# DMUX.net
KiCad netlist of a schematic drawn in EAGLE
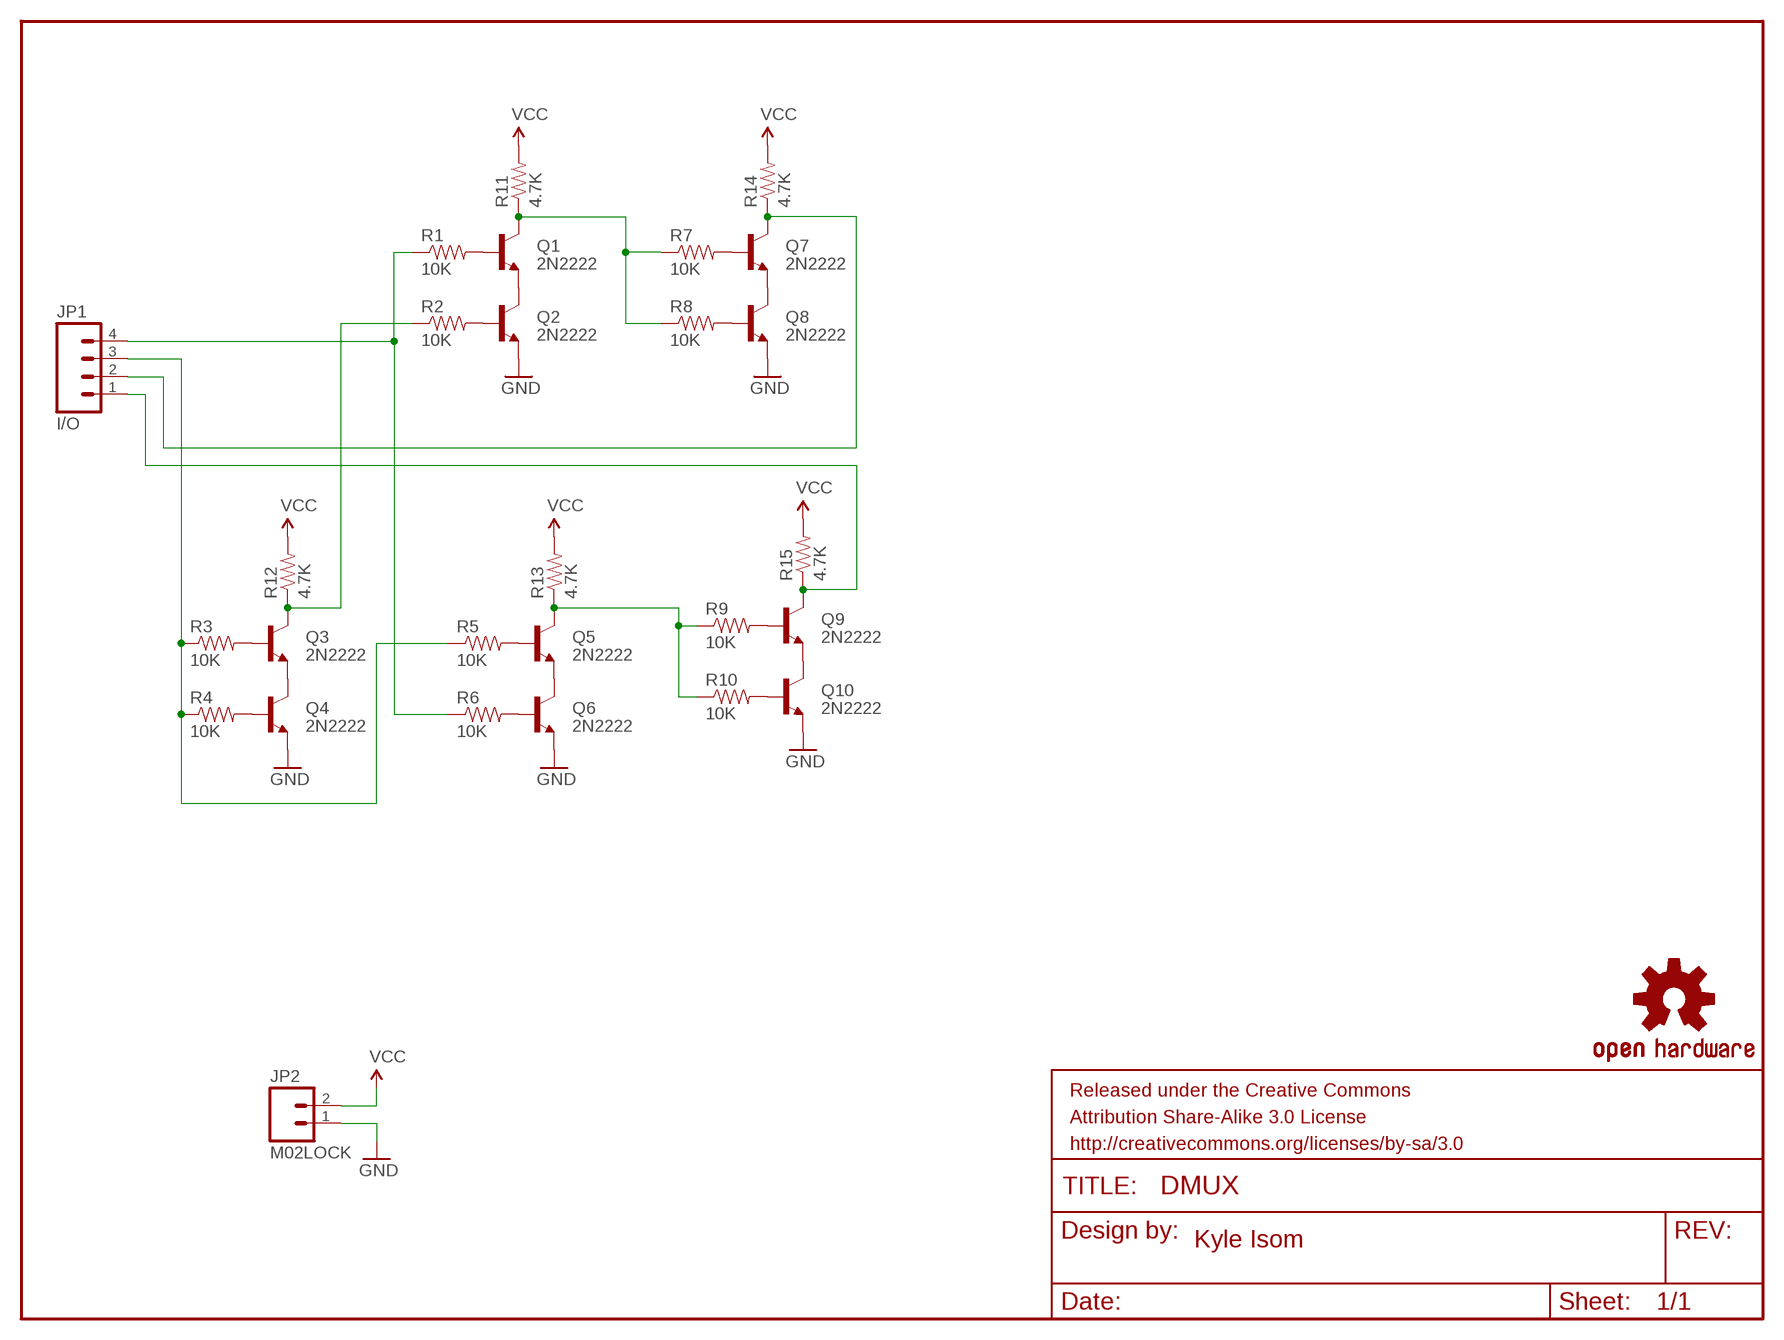
[diagram p0: schematic, sheet 1]

(export (version "E")
  (design (tool "Eeschema 10.0.6"))
  (components
    (comp (ref "FRAME1")
      (value "FRAME-LETTER")
      (footprint "eagle-import:CREATIVE_COMMONS")
      (libsource (lib "eagle-import") (part "FRAME-LETTER"))
    )
    (comp (ref "JP1")
      (value "I/O")
      (footprint "eagle-import:1X04_LOCK")
      (libsource (lib "eagle-import") (part "M04LOCK"))
    )
    (comp (ref "JP2")
      (value "M02LOCK")
      (footprint "eagle-import:1X02_LOCK")
      (libsource (lib "eagle-import") (part "M02LOCK"))
    )
    (comp (ref "LOGO1")
      (value "OSHW-LOGOS")
      (footprint "eagle-import:OSHW-LOGO-S")
      (libsource (lib "eagle-import") (part "OSHW-LOGOS"))
    )
    (comp (ref "Q1")
      (value "2N2222")
      (footprint "eagle-import:TO-92-AMMO")
      (libsource (lib "eagle-import") (part "TRANSISTOR_NPNTO-92-AMMO"))
    )
    (comp (ref "Q2")
      (value "2N2222")
      (footprint "eagle-import:TO-92-AMMO")
      (libsource (lib "eagle-import") (part "TRANSISTOR_NPNTO-92-AMMO"))
    )
    (comp (ref "Q3")
      (value "2N2222")
      (footprint "eagle-import:TO-92-AMMO")
      (libsource (lib "eagle-import") (part "TRANSISTOR_NPNTO-92-AMMO"))
    )
    (comp (ref "Q4")
      (value "2N2222")
      (footprint "eagle-import:TO-92-AMMO")
      (libsource (lib "eagle-import") (part "TRANSISTOR_NPNTO-92-AMMO"))
    )
    (comp (ref "Q5")
      (value "2N2222")
      (footprint "eagle-import:TO-92-AMMO")
      (libsource (lib "eagle-import") (part "TRANSISTOR_NPNTO-92-AMMO"))
    )
    (comp (ref "Q6")
      (value "2N2222")
      (footprint "eagle-import:TO-92-AMMO")
      (libsource (lib "eagle-import") (part "TRANSISTOR_NPNTO-92-AMMO"))
    )
    (comp (ref "Q7")
      (value "2N2222")
      (footprint "eagle-import:TO-92-AMMO")
      (libsource (lib "eagle-import") (part "TRANSISTOR_NPNTO-92-AMMO"))
    )
    (comp (ref "Q8")
      (value "2N2222")
      (footprint "eagle-import:TO-92-AMMO")
      (libsource (lib "eagle-import") (part "TRANSISTOR_NPNTO-92-AMMO"))
    )
    (comp (ref "Q9")
      (value "2N2222")
      (footprint "eagle-import:TO-92-AMMO")
      (libsource (lib "eagle-import") (part "TRANSISTOR_NPNTO-92-AMMO"))
    )
    (comp (ref "Q10")
      (value "2N2222")
      (footprint "eagle-import:TO-92-AMMO")
      (libsource (lib "eagle-import") (part "TRANSISTOR_NPNTO-92-AMMO"))
    )
    (comp (ref "R1")
      (value "10K")
      (footprint "eagle-import:AXIAL-0.4")
      (libsource (lib "eagle-import") (part "RESISTORPTH-1/4W"))
    )
    (comp (ref "R2")
      (value "10K")
      (footprint "eagle-import:AXIAL-0.4")
      (libsource (lib "eagle-import") (part "RESISTORPTH-1/4W"))
    )
    (comp (ref "R3")
      (value "10K")
      (footprint "eagle-import:AXIAL-0.4")
      (libsource (lib "eagle-import") (part "RESISTORPTH-1/4W"))
    )
    (comp (ref "R4")
      (value "10K")
      (footprint "eagle-import:AXIAL-0.4")
      (libsource (lib "eagle-import") (part "RESISTORPTH-1/4W"))
    )
    (comp (ref "R5")
      (value "10K")
      (footprint "eagle-import:AXIAL-0.4")
      (libsource (lib "eagle-import") (part "RESISTORPTH-1/4W"))
    )
    (comp (ref "R6")
      (value "10K")
      (footprint "eagle-import:AXIAL-0.4")
      (libsource (lib "eagle-import") (part "RESISTORPTH-1/4W"))
    )
    (comp (ref "R7")
      (value "10K")
      (footprint "eagle-import:AXIAL-0.4")
      (libsource (lib "eagle-import") (part "RESISTORPTH-1/4W"))
    )
    (comp (ref "R8")
      (value "10K")
      (footprint "eagle-import:AXIAL-0.4")
      (libsource (lib "eagle-import") (part "RESISTORPTH-1/4W"))
    )
    (comp (ref "R9")
      (value "10K")
      (footprint "eagle-import:AXIAL-0.4")
      (libsource (lib "eagle-import") (part "RESISTORPTH-1/4W"))
    )
    (comp (ref "R10")
      (value "10K")
      (footprint "eagle-import:AXIAL-0.4")
      (libsource (lib "eagle-import") (part "RESISTORPTH-1/4W"))
    )
    (comp (ref "R11")
      (value "4.7K")
      (footprint "eagle-import:AXIAL-0.4")
      (libsource (lib "eagle-import") (part "RESISTORPTH-1/4W"))
    )
    (comp (ref "R12")
      (value "4.7K")
      (footprint "eagle-import:AXIAL-0.4")
      (libsource (lib "eagle-import") (part "RESISTORPTH-1/4W"))
    )
    (comp (ref "R13")
      (value "4.7K")
      (footprint "eagle-import:AXIAL-0.4")
      (libsource (lib "eagle-import") (part "RESISTORPTH-1/4W"))
    )
    (comp (ref "R14")
      (value "4.7K")
      (footprint "eagle-import:AXIAL-0.4")
      (libsource (lib "eagle-import") (part "RESISTORPTH-1/4W"))
    )
    (comp (ref "R15")
      (value "4.7K")
      (footprint "eagle-import:AXIAL-0.4")
      (libsource (lib "eagle-import") (part "RESISTORPTH-1/4W"))
    )
  )
  (nets
    (net (code "1") (name "GND") (class "Default")
      (node (ref "JP2") (pin "1") (pinfunction "1_1") (pintype "passive"))
      (node (ref "Q10") (pin "1") (pinfunction "E_1") (pintype "passive"))
      (node (ref "Q2") (pin "1") (pinfunction "E_1") (pintype "passive"))
      (node (ref "Q4") (pin "1") (pinfunction "E_1") (pintype "passive"))
      (node (ref "Q6") (pin "1") (pinfunction "E_1") (pintype "passive"))
      (node (ref "Q8") (pin "1") (pinfunction "E_1") (pintype "passive"))
    )
    (net (code "2") (name "Net-(Q1-B)") (class "Default")
      (node (ref "Q1") (pin "2") (pinfunction "B_2") (pintype "passive"))
      (node (ref "R1") (pin "P$2") (pinfunction "2_P$2") (pintype "passive"))
    )
    (net (code "3") (name "Net-(Q1-C)") (class "Default")
      (node (ref "Q1") (pin "3") (pinfunction "C_3") (pintype "passive"))
      (node (ref "R11") (pin "P$1") (pinfunction "1_P$1") (pintype "passive"))
      (node (ref "R7") (pin "P$1") (pinfunction "1_P$1") (pintype "passive"))
      (node (ref "R8") (pin "P$1") (pinfunction "1_P$1") (pintype "passive"))
    )
    (net (code "4") (name "Net-(Q1-E)") (class "Default")
      (node (ref "Q1") (pin "1") (pinfunction "E_1") (pintype "passive"))
      (node (ref "Q2") (pin "3") (pinfunction "C_3") (pintype "passive"))
    )
    (net (code "5") (name "Net-(Q2-B)") (class "Default")
      (node (ref "Q2") (pin "2") (pinfunction "B_2") (pintype "passive"))
      (node (ref "R2") (pin "P$2") (pinfunction "2_P$2") (pintype "passive"))
    )
    (net (code "6") (name "Net-(Q3-B)") (class "Default")
      (node (ref "Q3") (pin "2") (pinfunction "B_2") (pintype "passive"))
      (node (ref "R3") (pin "P$2") (pinfunction "2_P$2") (pintype "passive"))
    )
    (net (code "7") (name "Net-(Q3-C)") (class "Default")
      (node (ref "Q3") (pin "3") (pinfunction "C_3") (pintype "passive"))
      (node (ref "R12") (pin "P$1") (pinfunction "1_P$1") (pintype "passive"))
      (node (ref "R2") (pin "P$1") (pinfunction "1_P$1") (pintype "passive"))
    )
    (net (code "8") (name "Net-(Q3-E)") (class "Default")
      (node (ref "Q3") (pin "1") (pinfunction "E_1") (pintype "passive"))
      (node (ref "Q4") (pin "3") (pinfunction "C_3") (pintype "passive"))
    )
    (net (code "9") (name "Net-(Q4-B)") (class "Default")
      (node (ref "Q4") (pin "2") (pinfunction "B_2") (pintype "passive"))
      (node (ref "R4") (pin "P$2") (pinfunction "2_P$2") (pintype "passive"))
    )
    (net (code "10") (name "Net-(Q5-B)") (class "Default")
      (node (ref "Q5") (pin "2") (pinfunction "B_2") (pintype "passive"))
      (node (ref "R5") (pin "P$2") (pinfunction "2_P$2") (pintype "passive"))
    )
    (net (code "11") (name "Net-(Q5-C)") (class "Default")
      (node (ref "Q5") (pin "3") (pinfunction "C_3") (pintype "passive"))
      (node (ref "R10") (pin "P$1") (pinfunction "1_P$1") (pintype "passive"))
      (node (ref "R13") (pin "P$1") (pinfunction "1_P$1") (pintype "passive"))
      (node (ref "R9") (pin "P$1") (pinfunction "1_P$1") (pintype "passive"))
    )
    (net (code "12") (name "Net-(Q5-E)") (class "Default")
      (node (ref "Q5") (pin "1") (pinfunction "E_1") (pintype "passive"))
      (node (ref "Q6") (pin "3") (pinfunction "C_3") (pintype "passive"))
    )
    (net (code "13") (name "Net-(Q6-B)") (class "Default")
      (node (ref "Q6") (pin "2") (pinfunction "B_2") (pintype "passive"))
      (node (ref "R6") (pin "P$2") (pinfunction "2_P$2") (pintype "passive"))
    )
    (net (code "14") (name "Net-(Q7-B)") (class "Default")
      (node (ref "Q7") (pin "2") (pinfunction "B_2") (pintype "passive"))
      (node (ref "R7") (pin "P$2") (pinfunction "2_P$2") (pintype "passive"))
    )
    (net (code "15") (name "Net-(Q7-C)") (class "Default")
      (node (ref "JP1") (pin "2") (pinfunction "2_2") (pintype "passive"))
      (node (ref "Q7") (pin "3") (pinfunction "C_3") (pintype "passive"))
      (node (ref "R14") (pin "P$1") (pinfunction "1_P$1") (pintype "passive"))
    )
    (net (code "16") (name "Net-(Q7-E)") (class "Default")
      (node (ref "Q7") (pin "1") (pinfunction "E_1") (pintype "passive"))
      (node (ref "Q8") (pin "3") (pinfunction "C_3") (pintype "passive"))
    )
    (net (code "17") (name "Net-(Q8-B)") (class "Default")
      (node (ref "Q8") (pin "2") (pinfunction "B_2") (pintype "passive"))
      (node (ref "R8") (pin "P$2") (pinfunction "2_P$2") (pintype "passive"))
    )
    (net (code "18") (name "Net-(Q9-B)") (class "Default")
      (node (ref "Q9") (pin "2") (pinfunction "B_2") (pintype "passive"))
      (node (ref "R9") (pin "P$2") (pinfunction "2_P$2") (pintype "passive"))
    )
    (net (code "19") (name "Net-(Q9-C)") (class "Default")
      (node (ref "JP1") (pin "1") (pinfunction "1_1") (pintype "passive"))
      (node (ref "Q9") (pin "3") (pinfunction "C_3") (pintype "passive"))
      (node (ref "R15") (pin "P$1") (pinfunction "1_P$1") (pintype "passive"))
    )
    (net (code "20") (name "Net-(Q10-B)") (class "Default")
      (node (ref "Q10") (pin "2") (pinfunction "B_2") (pintype "passive"))
      (node (ref "R10") (pin "P$2") (pinfunction "2_P$2") (pintype "passive"))
    )
    (net (code "21") (name "Net-(Q10-C)") (class "Default")
      (node (ref "Q10") (pin "3") (pinfunction "C_3") (pintype "passive"))
      (node (ref "Q9") (pin "1") (pinfunction "E_1") (pintype "passive"))
    )
    (net (code "22") (name "Net-(R1-1)") (class "Default")
      (node (ref "JP1") (pin "4") (pinfunction "4_4") (pintype "passive"))
      (node (ref "R1") (pin "P$1") (pinfunction "1_P$1") (pintype "passive"))
      (node (ref "R6") (pin "P$1") (pinfunction "1_P$1") (pintype "passive"))
    )
    (net (code "23") (name "Net-(R3-1)") (class "Default")
      (node (ref "JP1") (pin "3") (pinfunction "3_3") (pintype "passive"))
      (node (ref "R3") (pin "P$1") (pinfunction "1_P$1") (pintype "passive"))
      (node (ref "R4") (pin "P$1") (pinfunction "1_P$1") (pintype "passive"))
      (node (ref "R5") (pin "P$1") (pinfunction "1_P$1") (pintype "passive"))
    )
    (net (code "24") (name "VCC") (class "Default")
      (node (ref "JP2") (pin "2") (pinfunction "2_2") (pintype "passive"))
      (node (ref "R11") (pin "P$2") (pinfunction "2_P$2") (pintype "passive"))
      (node (ref "R12") (pin "P$2") (pinfunction "2_P$2") (pintype "passive"))
      (node (ref "R13") (pin "P$2") (pinfunction "2_P$2") (pintype "passive"))
      (node (ref "R14") (pin "P$2") (pinfunction "2_P$2") (pintype "passive"))
      (node (ref "R15") (pin "P$2") (pinfunction "2_P$2") (pintype "passive"))
    )
  )
)
